# Power_Circuit.net
KiCad netlist of a schematic drawn in Altium Designer
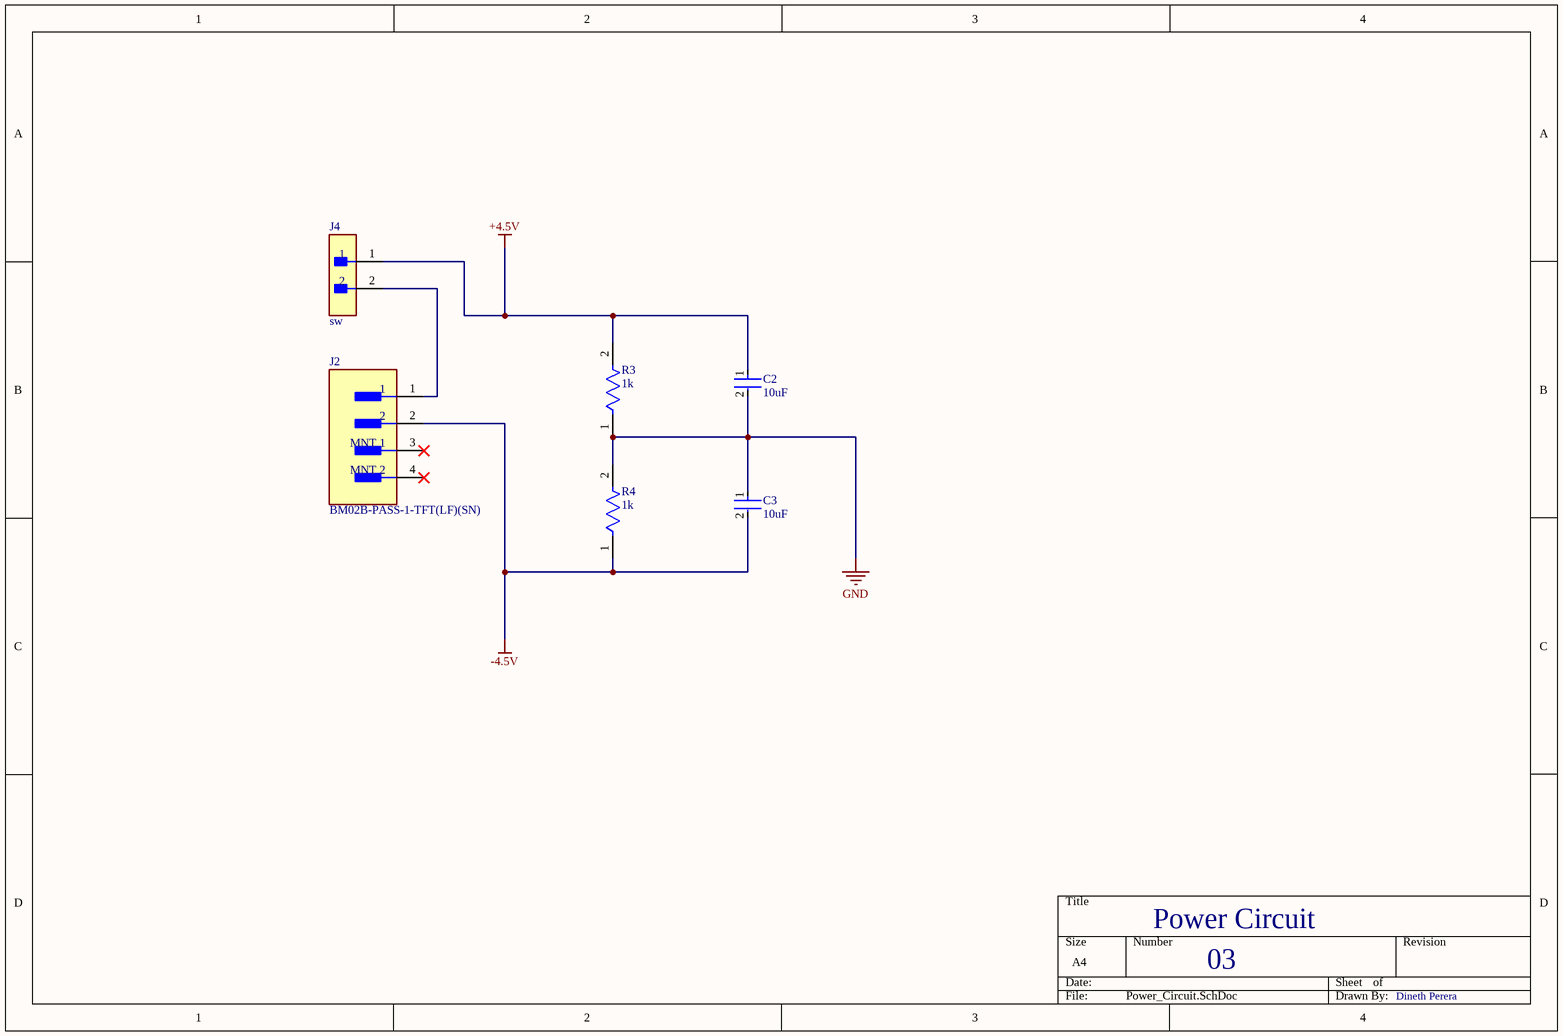
[diagram p0: Power_Circuit.SchDoc]

(export (version "E")
  (design (tool "Eeschema 10.0.6"))
  (components
    (comp (ref "C2")
      (value "10uF")
      (footprint "FP-GRM21B-0_1-IPC_C")
      (description "Chip Multilayer Ceramic Capacitors for General Purpose, 0805, 10uF, X5R, 15%, 10%, 16V")
      (fields (field (name "TOLERANCE") "10%") (field (name "VOLTAGE") "16V"))
      (libsource (lib "Altium Content Vault") (part "b4654b650e69147ec39a6b967a45e02"))
    )
    (comp (ref "C3")
      (value "10uF")
      (footprint "FP-GRM21B-0_1-IPC_C")
      (description "Chip Multilayer Ceramic Capacitors for General Purpose, 0805, 10uF, X5R, 15%, 10%, 16V")
      (fields (field (name "TOLERANCE") "10%") (field (name "VOLTAGE") "16V"))
      (libsource (lib "Altium Content Vault") (part "b4654b650e69147ec39a6b967a45e02"))
    )
    (comp (ref "J2")
      (value "BM02B-PASS-1-TFT(LF)(SN)")
      (footprint "FP-BM02B-PASS-1-TFT_LF_S-MFG")
      (description "CONN HEADER SMD 2POS 2MM")
      (libsource (lib "Altium Content Vault") (part "6ebc6fc72a9fd5a6899c7600f385cff"))
    )
    (comp (ref "J4")
      (value "sw")
      (footprint "FP-B02B-PASK-1_LF_SN-MFG")
      (description "CONN HEADER VERT 2POS 2MM")
      (libsource (lib "Altium Content Vault") (part "3bc925449376181038e59eaffc5286c"))
    )
    (comp (ref "R3")
      (value "1k")
      (footprint "FP-ERA6A-IPC_C")
      (description "RES 1K OHM 0.1% 1/8W 0805")
      (fields (field (name "TOLERANCE") "0.1%"))
      (libsource (lib "Altium Content Vault") (part "1029c3af85768c4190bb7ad29bc67b5"))
    )
    (comp (ref "R4")
      (value "1k")
      (footprint "FP-ERA6A-IPC_C")
      (description "RES 1K OHM 0.1% 1/8W 0805")
      (fields (field (name "TOLERANCE") "0.1%"))
      (libsource (lib "Altium Content Vault") (part "1029c3af85768c4190bb7ad29bc67b5"))
    )
  )
  (nets
    (net (code "1") (name "+4.5V") (class "Default")
      (node (ref "C2") (pin "1") (pinfunction "1_1") (pintype "passive"))
      (node (ref "J4") (pin "1") (pinfunction "1_1") (pintype "passive"))
      (node (ref "R3") (pin "2") (pinfunction "2_2") (pintype "passive"))
    )
    (net (code "2") (name "-4.5V") (class "Default")
      (node (ref "C3") (pin "2") (pinfunction "2_2") (pintype "passive"))
      (node (ref "J2") (pin "2") (pinfunction "2_2") (pintype "passive"))
      (node (ref "R4") (pin "1") (pinfunction "1_1") (pintype "passive"))
    )
    (net (code "3") (name "GND") (class "Default")
      (node (ref "C2") (pin "2") (pinfunction "2_2") (pintype "passive"))
      (node (ref "C3") (pin "1") (pinfunction "1_1") (pintype "passive"))
      (node (ref "R3") (pin "1") (pinfunction "1_1") (pintype "passive"))
      (node (ref "R4") (pin "2") (pinfunction "2_2") (pintype "passive"))
    )
    (net (code "4") (name "Net-(J2-Pad1)") (class "Default")
      (node (ref "J2") (pin "1") (pinfunction "1_1") (pintype "passive"))
      (node (ref "J4") (pin "2") (pinfunction "2_2") (pintype "passive"))
    )
    (net (code "5") (name "unconnected-(J2-MNT_1-Pad3)") (class "Default")
      (node (ref "J2") (pin "3") (pinfunction "MNT_1_3") (pintype "passive+no_connect"))
    )
    (net (code "6") (name "unconnected-(J2-MNT_2-Pad4)") (class "Default")
      (node (ref "J2") (pin "4") (pinfunction "MNT_2_4") (pintype "passive+no_connect"))
    )
  )
)
